# Adafruit_MCP4728.net
KiCad netlist of a schematic drawn in EAGLE
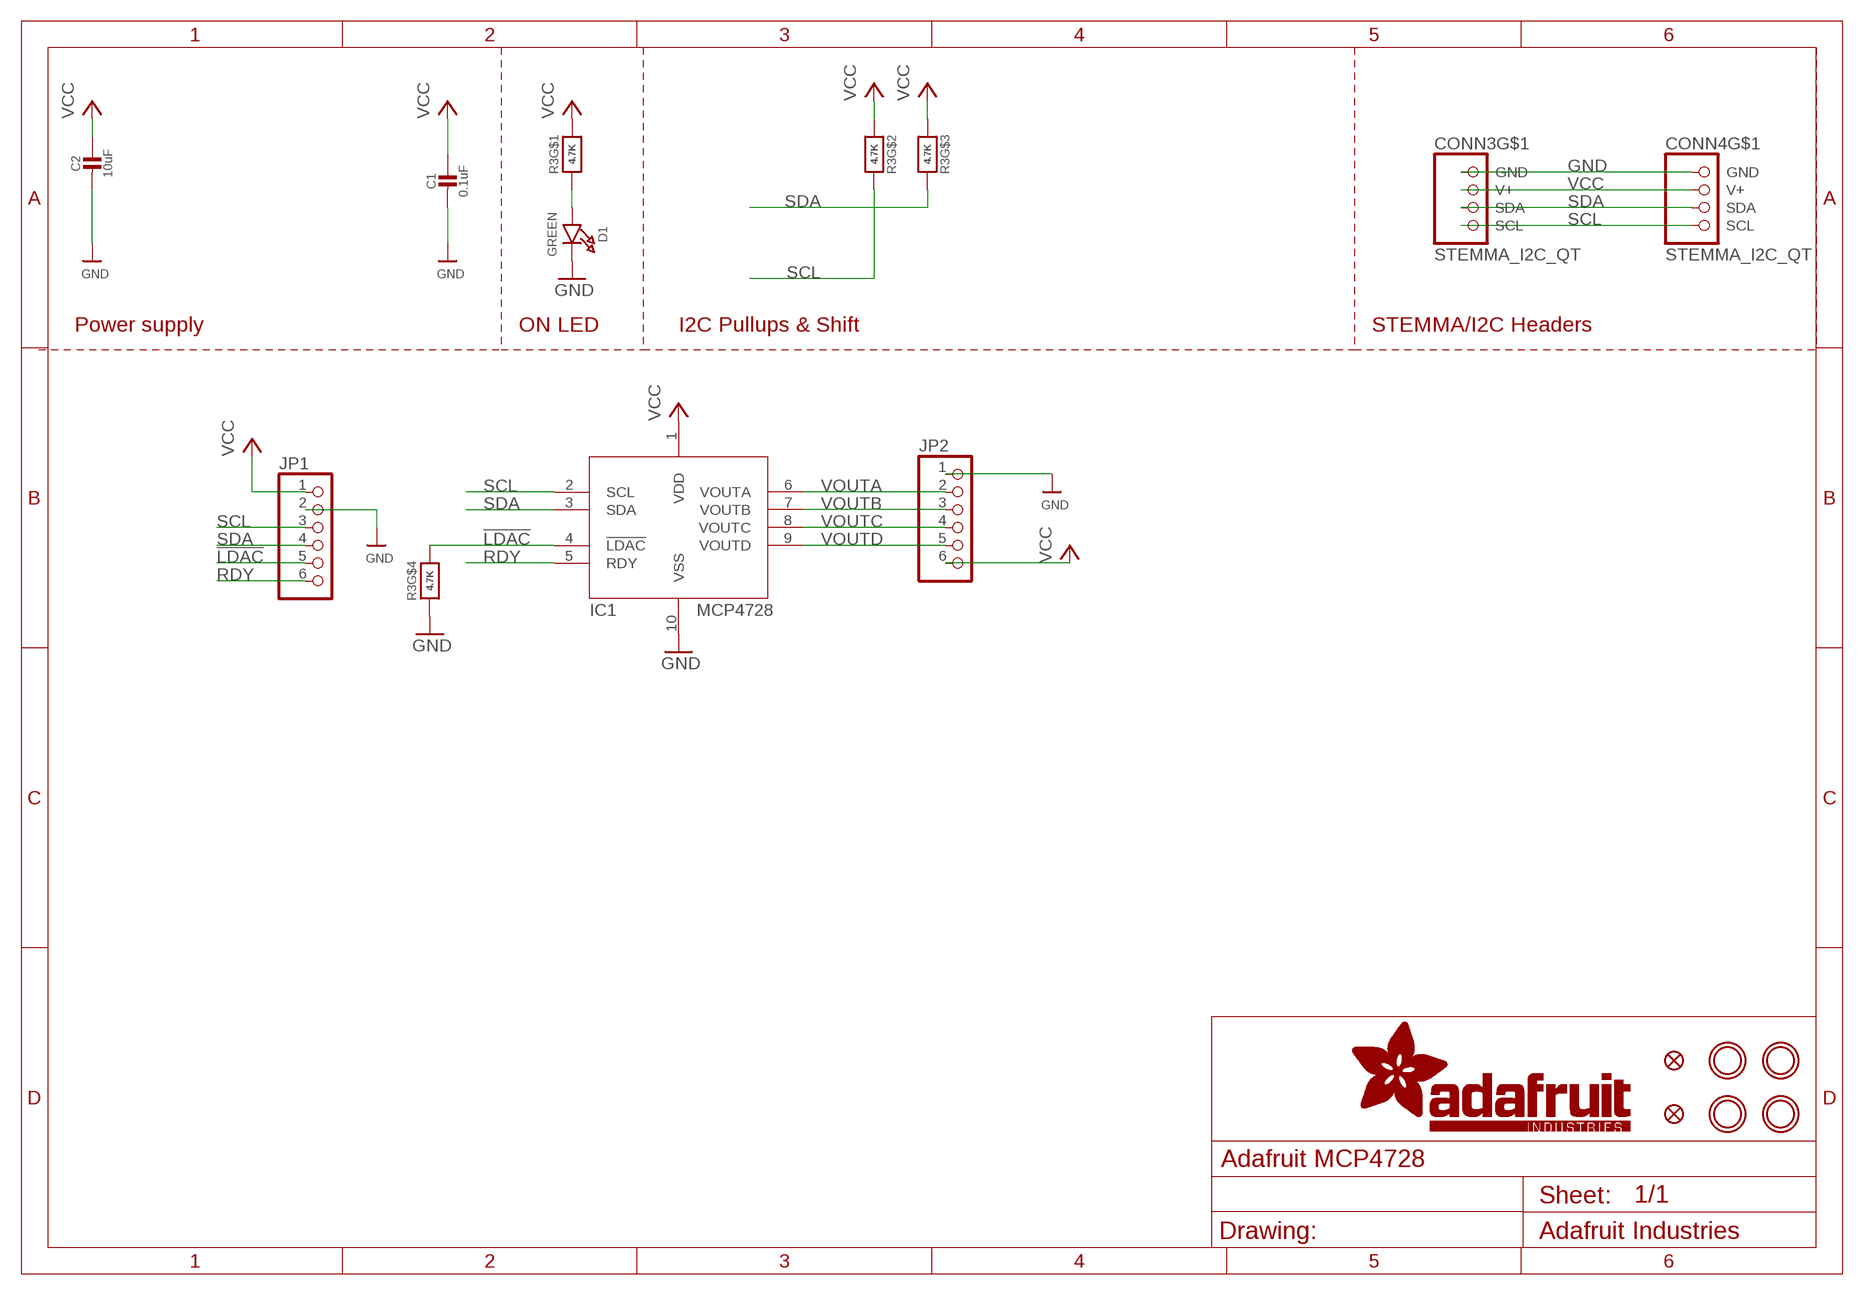
[diagram p0: schematic, sheet 1]

(export (version "E")
  (design (tool "Eeschema 10.0.6"))
  (components
    (comp (ref "C1")
      (value "0.1uF")
      (footprint "eagle-import:0603-NO")
      (libsource (lib "eagle-import") (part "CAP_CERAMIC0603_NO"))
    )
    (comp (ref "C2")
      (value "10uF")
      (footprint "eagle-import:0805-NO")
      (libsource (lib "eagle-import") (part "CAP_CERAMIC0805-NOOUTLINE"))
    )
    (comp (ref "CONN3")
      (value "STEMMA_I2C_QT")
      (footprint "eagle-import:JST_SH4")
      (libsource (lib "eagle-import") (part "STEMMA_I2C_QT"))
    )
    (comp (ref "CONN4")
      (value "STEMMA_I2C_QT")
      (footprint "eagle-import:JST_SH4")
      (libsource (lib "eagle-import") (part "STEMMA_I2C_QT"))
    )
    (comp (ref "D1")
      (value "GREEN")
      (footprint "eagle-import:CHIPLED_0603_NOOUTLINE")
      (libsource (lib "eagle-import") (part "LED0603_NOOUTLINE"))
    )
    (comp (ref "FID3")
      (value "FIDUCIAL_1MM")
      (footprint "eagle-import:FIDUCIAL_1MM")
      (libsource (lib "eagle-import") (part "FIDUCIAL_1MM"))
    )
    (comp (ref "FID4")
      (value "FIDUCIAL_1MM")
      (footprint "eagle-import:FIDUCIAL_1MM")
      (libsource (lib "eagle-import") (part "FIDUCIAL_1MM"))
    )
    (comp (ref "IC1")
      (value "MCP4728")
      (footprint "eagle-import:MSOP10")
      (libsource (lib "eagle-import") (part "MCP4728"))
    )
    (comp (ref "JP1")
      (value "HEADER-1X670MIL")
      (footprint "eagle-import:1X06_ROUND_70")
      (libsource (lib "eagle-import") (part "HEADER-1X670MIL"))
    )
    (comp (ref "JP2")
      (value "HEADER-1X670MIL")
      (footprint "eagle-import:1X06_ROUND_70")
      (libsource (lib "eagle-import") (part "HEADER-1X670MIL"))
    )
    (comp (ref "R3")
      (value "4.7K")
      (footprint "eagle-import:RESPACK_4X0603")
      (libsource (lib "eagle-import") (part "RESISTOR_4PACK"))
    )
    (comp (ref "U$1")
      (value "MOUNTINGHOLE2.5")
      (footprint "eagle-import:MOUNTINGHOLE_2.5_PLATED")
      (libsource (lib "eagle-import") (part "MOUNTINGHOLE2.5"))
    )
    (comp (ref "U$17")
      (value "MOUNTINGHOLE2.5")
      (footprint "eagle-import:MOUNTINGHOLE_2.5_PLATED")
      (libsource (lib "eagle-import") (part "MOUNTINGHOLE2.5"))
    )
    (comp (ref "U$19")
      (value "MOUNTINGHOLE2.5")
      (footprint "eagle-import:MOUNTINGHOLE_2.5_PLATED")
      (libsource (lib "eagle-import") (part "MOUNTINGHOLE2.5"))
    )
    (comp (ref "U$21")
      (value "MOUNTINGHOLE2.5")
      (footprint "eagle-import:MOUNTINGHOLE_2.5_PLATED")
      (libsource (lib "eagle-import") (part "MOUNTINGHOLE2.5"))
    )
  )
  (nets
    (net (code "1") (name "/RDY") (class "Default")
      (node (ref "IC1") (pin "5") (pinfunction "RDY_5") (pintype "output"))
      (node (ref "JP1") (pin "6") (pinfunction "6_6") (pintype "passive"))
    )
    (net (code "2") (name "/SCL") (class "Default")
      (node (ref "CONN3") (pin "4") (pinfunction "SCL_4") (pintype "passive"))
      (node (ref "CONN4") (pin "4") (pinfunction "SCL_4") (pintype "passive"))
      (node (ref "IC1") (pin "2") (pinfunction "SCL_2") (pintype "bidirectional"))
      (node (ref "JP1") (pin "3") (pinfunction "3_3") (pintype "passive"))
      (node (ref "R3") (pin "7") (pinfunction "2_7") (pintype "passive"))
    )
    (net (code "3") (name "/SDA") (class "Default")
      (node (ref "CONN3") (pin "3") (pinfunction "SDA_3") (pintype "passive"))
      (node (ref "CONN4") (pin "3") (pinfunction "SDA_3") (pintype "passive"))
      (node (ref "IC1") (pin "3") (pinfunction "SDA_3") (pintype "bidirectional"))
      (node (ref "JP1") (pin "4") (pinfunction "4_4") (pintype "passive"))
      (node (ref "R3") (pin "6") (pinfunction "2_6") (pintype "passive"))
    )
    (net (code "4") (name "/VOUTA") (class "Default")
      (node (ref "IC1") (pin "6") (pinfunction "VOUTA_6") (pintype "output"))
      (node (ref "JP2") (pin "2") (pinfunction "2_2") (pintype "passive"))
    )
    (net (code "5") (name "/VOUTB") (class "Default")
      (node (ref "IC1") (pin "7") (pinfunction "VOUTB_7") (pintype "output"))
      (node (ref "JP2") (pin "3") (pinfunction "3_3") (pintype "passive"))
    )
    (net (code "6") (name "/VOUTC") (class "Default")
      (node (ref "IC1") (pin "8") (pinfunction "VOUTC_8") (pintype "output"))
      (node (ref "JP2") (pin "4") (pinfunction "4_4") (pintype "passive"))
    )
    (net (code "7") (name "/VOUTD") (class "Default")
      (node (ref "IC1") (pin "9") (pinfunction "VOUTD_9") (pintype "output"))
      (node (ref "JP2") (pin "5") (pinfunction "5_5") (pintype "passive"))
    )
    (net (code "8") (name "/~{LDAC}") (class "Default")
      (node (ref "IC1") (pin "4") (pinfunction "~{LDAC}_4") (pintype "input"))
      (node (ref "JP1") (pin "5") (pinfunction "5_5") (pintype "passive"))
      (node (ref "R3") (pin "5") (pinfunction "2_5") (pintype "passive"))
    )
    (net (code "9") (name "GND") (class "Default")
      (node (ref "C1") (pin "2") (pinfunction "2_2") (pintype "passive"))
      (node (ref "C2") (pin "2") (pinfunction "2_2") (pintype "passive"))
      (node (ref "CONN3") (pin "1") (pinfunction "GND_1") (pintype "passive"))
      (node (ref "CONN4") (pin "1") (pinfunction "GND_1") (pintype "passive"))
      (node (ref "D1") (pin "C") (pinfunction "C_C") (pintype "passive"))
      (node (ref "IC1") (pin "10") (pinfunction "VSS_10") (pintype "power_in"))
      (node (ref "JP1") (pin "2") (pinfunction "2_2") (pintype "passive"))
      (node (ref "JP2") (pin "1") (pinfunction "1_1") (pintype "passive"))
      (node (ref "R3") (pin "4") (pinfunction "1_4") (pintype "passive"))
    )
    (net (code "10") (name "Net-(D1-PadA)") (class "Default")
      (node (ref "D1") (pin "A") (pinfunction "A_A") (pintype "passive"))
      (node (ref "R3") (pin "1") (pinfunction "1_1") (pintype "passive"))
    )
    (net (code "11") (name "VCC") (class "Default")
      (node (ref "C1") (pin "1") (pinfunction "1_1") (pintype "passive"))
      (node (ref "C2") (pin "1") (pinfunction "1_1") (pintype "passive"))
      (node (ref "CONN3") (pin "2") (pinfunction "V+_2") (pintype "passive"))
      (node (ref "CONN4") (pin "2") (pinfunction "V+_2") (pintype "passive"))
      (node (ref "IC1") (pin "1") (pinfunction "VDD_1") (pintype "power_in"))
      (node (ref "JP1") (pin "1") (pinfunction "1_1") (pintype "passive"))
      (node (ref "JP2") (pin "6") (pinfunction "6_6") (pintype "passive"))
      (node (ref "R3") (pin "2") (pinfunction "1_2") (pintype "passive"))
      (node (ref "R3") (pin "3") (pinfunction "1_3") (pintype "passive"))
      (node (ref "R3") (pin "8") (pinfunction "2_8") (pintype "passive"))
    )
  )
)
